# RobotCtrl_V2_Core-board.net
KiCad netlist of a schematic drawn in Altium Designer
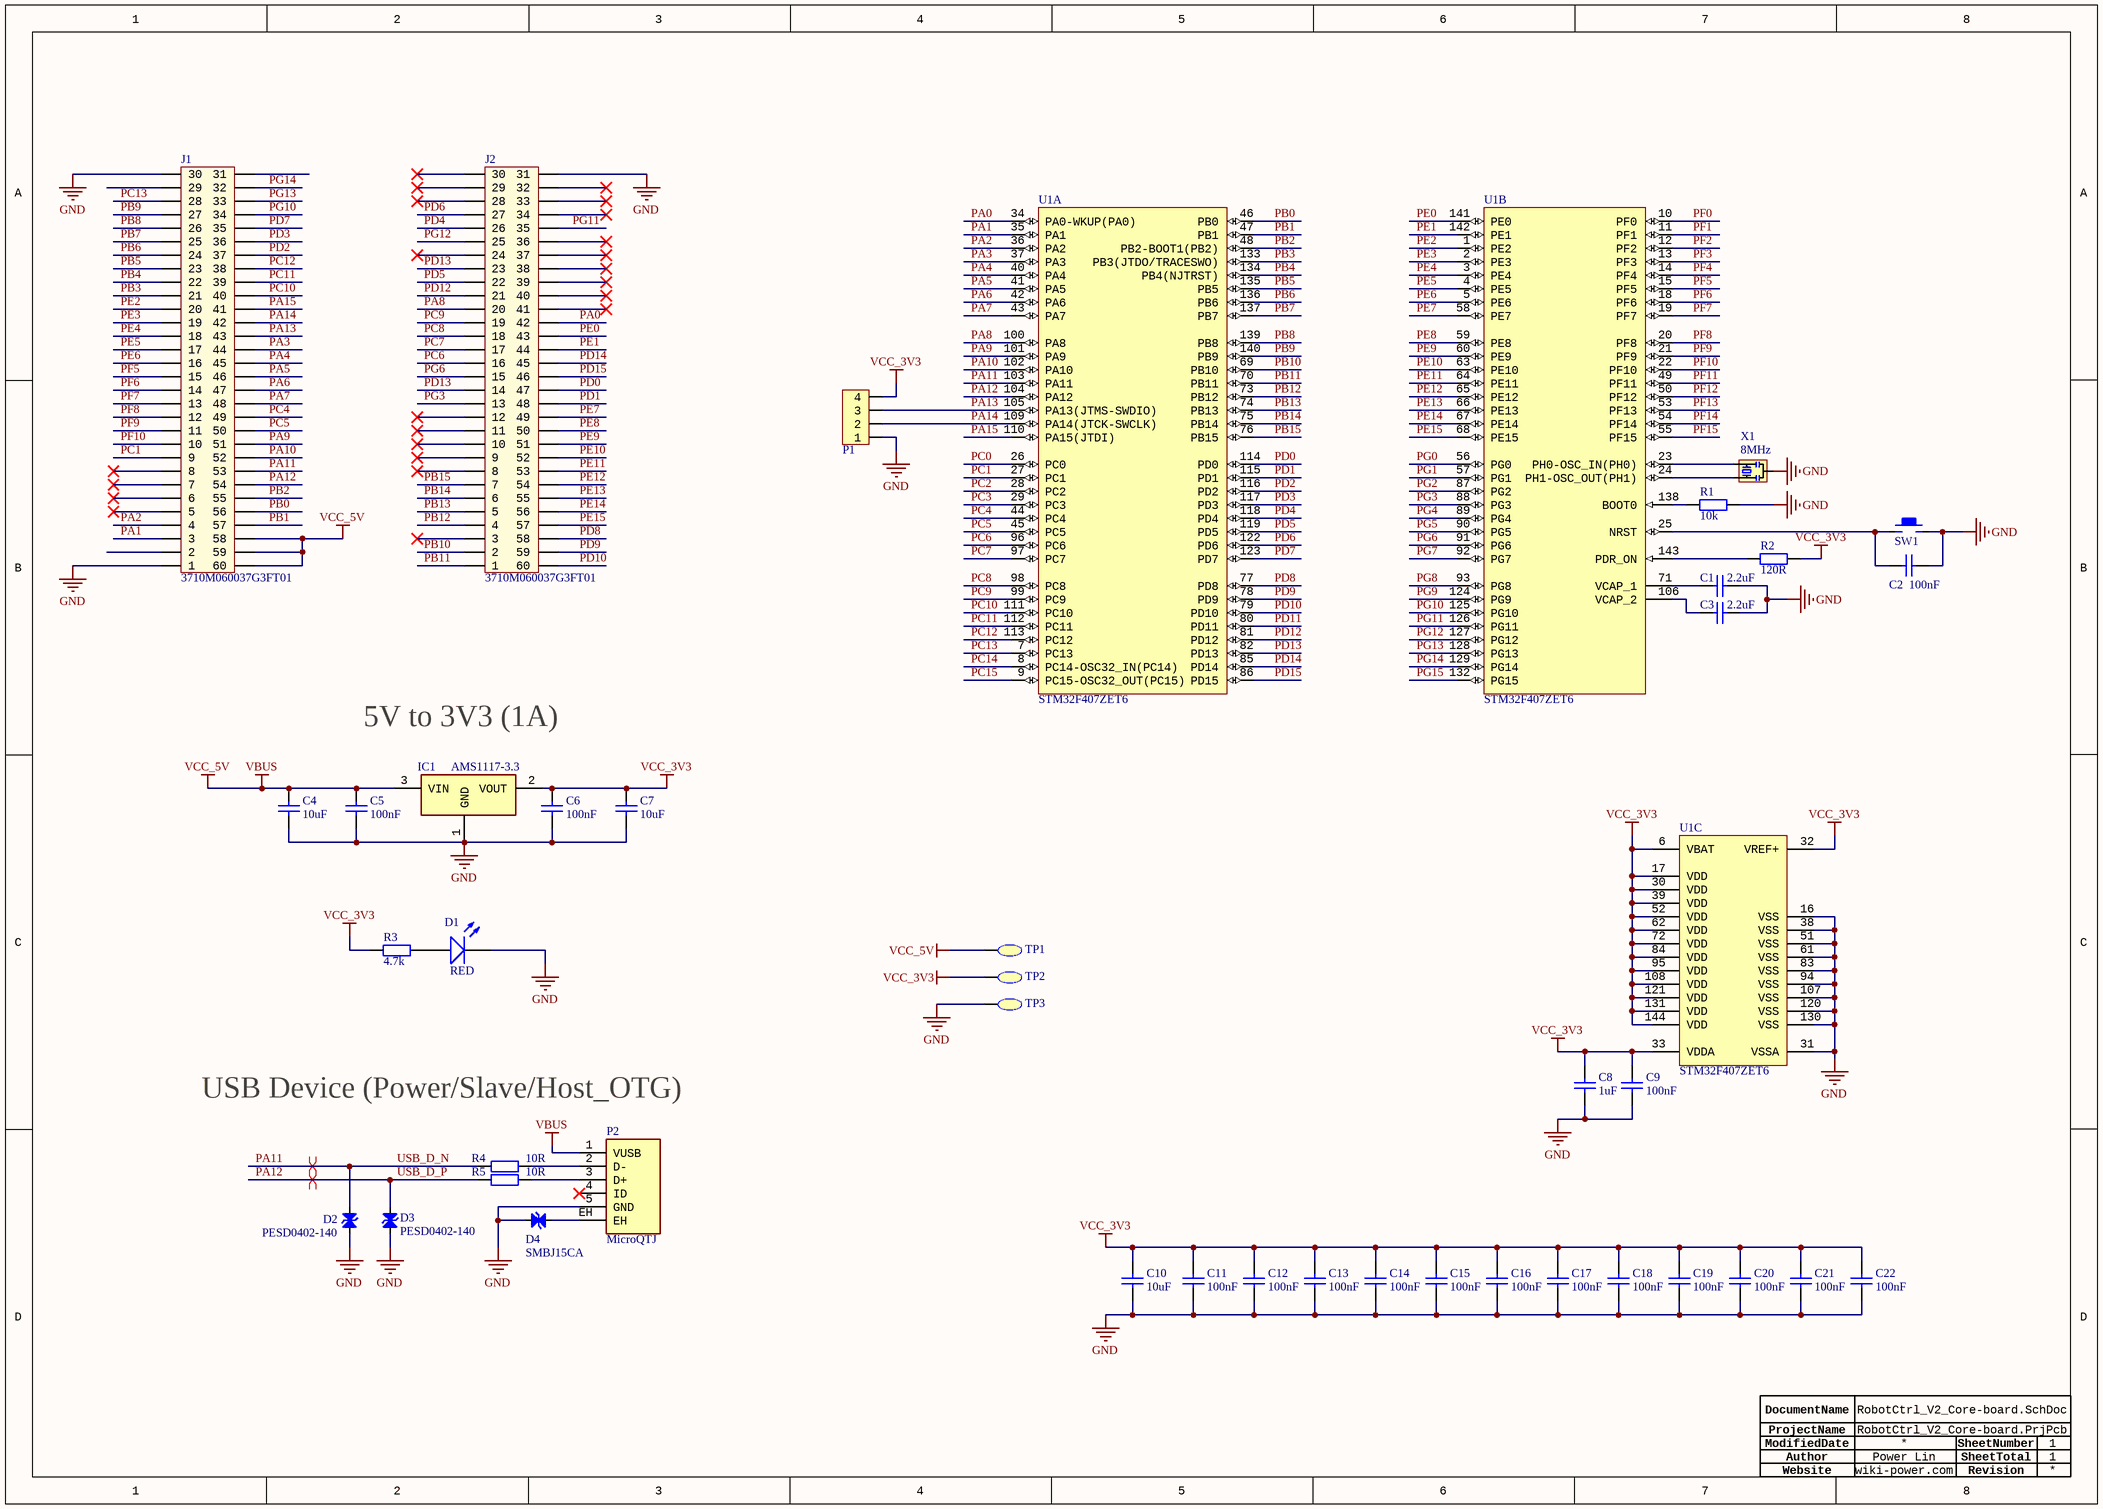
[diagram p0: RobotCtrl_V2_Core-board.SchDoc]

(export (version "E")
  (design (tool "Eeschema 10.0.6"))
  (components
    (comp (ref "C1")
      (value "2.2uF")
      (footprint "CAP-0603")
      (description "贴片电容")
      (libsource (lib "Power_Lib_Altium") (part "CAP"))
    )
    (comp (ref "C2")
      (value "100nF")
      (footprint "CAP-0603")
      (description "贴片电容")
      (libsource (lib "Power_Lib_Altium") (part "CAP"))
    )
    (comp (ref "C3")
      (value "2.2uF")
      (footprint "CAP-0603")
      (description "贴片电容")
      (libsource (lib "Power_Lib_Altium") (part "CAP"))
    )
    (comp (ref "C4")
      (value "10uF")
      (footprint "CAP-0603")
      (description "贴片电容")
      (libsource (lib "Power_Lib_Altium") (part "CAP"))
    )
    (comp (ref "C5")
      (value "100nF")
      (footprint "CAP-0603")
      (description "贴片电容")
      (libsource (lib "Power_Lib_Altium") (part "CAP"))
    )
    (comp (ref "C6")
      (value "100nF")
      (footprint "CAP-0603")
      (description "贴片电容")
      (libsource (lib "Power_Lib_Altium") (part "CAP"))
    )
    (comp (ref "C7")
      (value "10uF")
      (footprint "CAP-0603")
      (description "贴片电容")
      (libsource (lib "Power_Lib_Altium") (part "CAP"))
    )
    (comp (ref "C8")
      (value "1uF")
      (footprint "CAP-0603")
      (description "贴片电容")
      (libsource (lib "Power_Lib_Altium") (part "CAP"))
    )
    (comp (ref "C9")
      (value "100nF")
      (footprint "CAP-0603")
      (description "贴片电容")
      (libsource (lib "Power_Lib_Altium") (part "CAP"))
    )
    (comp (ref "C10")
      (value "10uF")
      (footprint "CAP-0603")
      (description "贴片电容")
      (libsource (lib "Power_Lib_Altium") (part "CAP"))
    )
    (comp (ref "C11")
      (value "100nF")
      (footprint "CAP-0603")
      (description "贴片电容")
      (libsource (lib "Power_Lib_Altium") (part "CAP"))
    )
    (comp (ref "C12")
      (value "100nF")
      (footprint "CAP-0603")
      (description "贴片电容")
      (libsource (lib "Power_Lib_Altium") (part "CAP"))
    )
    (comp (ref "C13")
      (value "100nF")
      (footprint "CAP-0603")
      (description "贴片电容")
      (libsource (lib "Power_Lib_Altium") (part "CAP"))
    )
    (comp (ref "C14")
      (value "100nF")
      (footprint "CAP-0603")
      (description "贴片电容")
      (libsource (lib "Power_Lib_Altium") (part "CAP"))
    )
    (comp (ref "C15")
      (value "100nF")
      (footprint "CAP-0603")
      (description "贴片电容")
      (libsource (lib "Power_Lib_Altium") (part "CAP"))
    )
    (comp (ref "C16")
      (value "100nF")
      (footprint "CAP-0603")
      (description "贴片电容")
      (libsource (lib "Power_Lib_Altium") (part "CAP"))
    )
    (comp (ref "C17")
      (value "100nF")
      (footprint "CAP-0603")
      (description "贴片电容")
      (libsource (lib "Power_Lib_Altium") (part "CAP"))
    )
    (comp (ref "C18")
      (value "100nF")
      (footprint "CAP-0603")
      (description "贴片电容")
      (libsource (lib "Power_Lib_Altium") (part "CAP"))
    )
    (comp (ref "C19")
      (value "100nF")
      (footprint "CAP-0603")
      (description "贴片电容")
      (libsource (lib "Power_Lib_Altium") (part "CAP"))
    )
    (comp (ref "C20")
      (value "100nF")
      (footprint "CAP-0603")
      (description "贴片电容")
      (libsource (lib "Power_Lib_Altium") (part "CAP"))
    )
    (comp (ref "C21")
      (value "100nF")
      (footprint "CAP-0603")
      (description "贴片电容")
      (libsource (lib "Power_Lib_Altium") (part "CAP"))
    )
    (comp (ref "C22")
      (value "100nF")
      (footprint "CAP-0603")
      (description "贴片电容")
      (libsource (lib "Power_Lib_Altium") (part "CAP"))
    )
    (comp (ref "D1")
      (value "RED")
      (footprint "LED-0603")
      (description "发光二极管")
      (libsource (lib "Power_Lib_Altium") (part "LED"))
    )
    (comp (ref "D2")
      (value "PESD0402-140")
      (footprint "D-0402")
      (libsource (lib "Power_Lib_Altium") (part "TVS_C"))
    )
    (comp (ref "D3")
      (value "PESD0402-140")
      (footprint "D-0402")
      (libsource (lib "Power_Lib_Altium") (part "TVS_C"))
    )
    (comp (ref "D4")
      (value "SMBJ15CA")
      (footprint "DO-214AA/SMB")
      (libsource (lib "Power_Lib_Altium") (part "TVS_C"))
    )
    (comp (ref "IC1")
      (value "AMS1117-3.3")
      (footprint "SOT-223")
      (description "AMS1117-3.3 1.0A")
      (fields (field (name "MANUFACTURER_PART_NUMBER") "SI2302DS") (field (name "RS PART NUMBER") "7983053P"))
      (libsource (lib "Power_Lib_Altium") (part "AMS1117"))
    )
    (comp (ref "J1")
      (value "3710M060037G3FT01")
      (footprint "3710M060037G3FT01")
      (description "B2B Connector")
      (libsource (lib "Power_Lib_Altium") (part "3710M/F"))
    )
    (comp (ref "J2")
      (value "3710M060037G3FT01")
      (footprint "3710M060037G3FT01")
      (description "B2B Connector")
      (libsource (lib "Power_Lib_Altium") (part "3710M/F"))
    )
    (comp (ref "P1")
      (value "HDR1x4_2.54")
      (footprint "HDR1x4_2.54_180")
      (description "Header")
      (libsource (lib "Power_Lib_Altium") (part "HDR1x4_2.54"))
    )
    (comp (ref "P2")
      (value "MicroQTJ")
      (footprint "USB-MICRO")
      (description "USB_MICRO")
      (libsource (lib "Power_Lib_Altium") (part "USB_MICRO"))
    )
    (comp (ref "R1")
      (value "10k")
      (footprint "R-0603")
      (description "贴片电阻")
      (libsource (lib "") (part "RES_1"))
    )
    (comp (ref "R2")
      (value "120R")
      (footprint "R-0603")
      (description "贴片电阻")
      (libsource (lib "") (part "RES_1"))
    )
    (comp (ref "R3")
      (value "4.7k")
      (footprint "R-0603")
      (description "贴片电阻")
      (libsource (lib "") (part "RES_1"))
    )
    (comp (ref "R4")
      (value "10R")
      (footprint "R-0603")
      (description "贴片电阻")
      (libsource (lib "Power_Lib_Altium") (part "RES"))
    )
    (comp (ref "R5")
      (value "10R")
      (footprint "R-0603")
      (description "贴片电阻")
      (libsource (lib "Power_Lib_Altium") (part "RES"))
    )
    (comp (ref "SW1")
      (value "KEY")
      (footprint "KEY-4P-4.2*3.4*2.5")
      (description "按键开关")
      (libsource (lib "Power_Lib_Altium") (part "KEY"))
    )
    (comp (ref "TP1")
      (value "TestPoint")
      (footprint "TestPoint")
      (description "测试点")
      (libsource (lib "Power_Lib_Altium") (part "TestPoint"))
    )
    (comp (ref "TP2")
      (value "TestPoint")
      (footprint "TestPoint")
      (description "测试点")
      (libsource (lib "Power_Lib_Altium") (part "TestPoint"))
    )
    (comp (ref "TP3")
      (value "TestPoint")
      (footprint "TestPoint")
      (description "测试点")
      (libsource (lib "Power_Lib_Altium") (part "TestPoint"))
    )
    (comp (ref "U1")
      (value "STM32F407ZET6")
      (footprint "STM-LQFP144_N")
      (fields (field (name "MANUFACTURER") "STMicroelectronics"))
      (libsource (lib "Power_Lib_Altium") (part "STM32F407ZET6"))
    )
    (comp (ref "X1")
      (value "8MHz")
      (footprint "SMD3213-3P")
      (description "CSTCE8M00G15C99-R0")
      (libsource (lib "Power_Lib_Altium") (part "XTAL"))
    )
  )
  (nets
    (net (code "1") (name "/PA0") (class "Default")
      (node (ref "J2") (pin "42") (pinfunction "42_42") (pintype "passive"))
      (node (ref "U1") (pin "34") (pinfunction "PA0-WKUP(PA0)_34") (pintype "bidirectional"))
    )
    (net (code "2") (name "/PA1") (class "Default")
      (node (ref "J1") (pin "3") (pinfunction "3_3") (pintype "passive"))
      (node (ref "U1") (pin "35") (pinfunction "PA1_35") (pintype "bidirectional"))
    )
    (net (code "3") (name "/PA2") (class "Default")
      (node (ref "J1") (pin "4") (pinfunction "4_4") (pintype "passive"))
      (node (ref "U1") (pin "36") (pinfunction "PA2_36") (pintype "bidirectional"))
    )
    (net (code "4") (name "/PA3") (class "Default")
      (node (ref "J1") (pin "44") (pinfunction "44_44") (pintype "passive"))
      (node (ref "U1") (pin "37") (pinfunction "PA3_37") (pintype "bidirectional"))
    )
    (net (code "5") (name "/PA4") (class "Default")
      (node (ref "J1") (pin "45") (pinfunction "45_45") (pintype "passive"))
      (node (ref "U1") (pin "40") (pinfunction "PA4_40") (pintype "bidirectional"))
    )
    (net (code "6") (name "/PA5") (class "Default")
      (node (ref "J1") (pin "46") (pinfunction "46_46") (pintype "passive"))
      (node (ref "U1") (pin "41") (pinfunction "PA5_41") (pintype "bidirectional"))
    )
    (net (code "7") (name "/PA6") (class "Default")
      (node (ref "J1") (pin "47") (pinfunction "47_47") (pintype "passive"))
      (node (ref "U1") (pin "42") (pinfunction "PA6_42") (pintype "bidirectional"))
    )
    (net (code "8") (name "/PA7") (class "Default")
      (node (ref "J1") (pin "48") (pinfunction "48_48") (pintype "passive"))
      (node (ref "U1") (pin "43") (pinfunction "PA7_43") (pintype "bidirectional"))
    )
    (net (code "9") (name "/PA8") (class "Default")
      (node (ref "J2") (pin "20") (pinfunction "20_20") (pintype "passive"))
      (node (ref "U1") (pin "100") (pinfunction "PA8_100") (pintype "bidirectional"))
    )
    (net (code "10") (name "/PA9") (class "Default")
      (node (ref "J1") (pin "51") (pinfunction "51_51") (pintype "passive"))
      (node (ref "U1") (pin "101") (pinfunction "PA9_101") (pintype "bidirectional"))
    )
    (net (code "11") (name "/PA10") (class "Default")
      (node (ref "J1") (pin "52") (pinfunction "52_52") (pintype "passive"))
      (node (ref "U1") (pin "102") (pinfunction "PA10_102") (pintype "bidirectional"))
    )
    (net (code "12") (name "/PA11") (class "Default")
      (node (ref "D2") (pin "2") (pinfunction "2_2") (pintype "passive"))
      (node (ref "J1") (pin "53") (pinfunction "53_53") (pintype "passive"))
      (node (ref "R4") (pin "1") (pinfunction "1_1") (pintype "passive"))
      (node (ref "U1") (pin "103") (pinfunction "PA11_103") (pintype "bidirectional"))
    )
    (net (code "13") (name "/PA12") (class "Default")
      (node (ref "D3") (pin "2") (pinfunction "2_2") (pintype "passive"))
      (node (ref "J1") (pin "54") (pinfunction "54_54") (pintype "passive"))
      (node (ref "R5") (pin "1") (pinfunction "1_1") (pintype "passive"))
      (node (ref "U1") (pin "104") (pinfunction "PA12_104") (pintype "bidirectional"))
    )
    (net (code "14") (name "/PA13") (class "Default")
      (node (ref "J1") (pin "43") (pinfunction "43_43") (pintype "passive"))
      (node (ref "P1") (pin "3") (pinfunction "3_3") (pintype "passive"))
      (node (ref "U1") (pin "105") (pinfunction "PA13(JTMS-SWDIO)_105") (pintype "bidirectional"))
    )
    (net (code "15") (name "/PA14") (class "Default")
      (node (ref "J1") (pin "42") (pinfunction "42_42") (pintype "passive"))
      (node (ref "P1") (pin "2") (pinfunction "2_2") (pintype "passive"))
      (node (ref "U1") (pin "109") (pinfunction "PA14(JTCK-SWCLK)_109") (pintype "bidirectional"))
    )
    (net (code "16") (name "/PA15") (class "Default")
      (node (ref "J1") (pin "41") (pinfunction "41_41") (pintype "passive"))
      (node (ref "U1") (pin "110") (pinfunction "PA15(JTDI)_110") (pintype "bidirectional"))
    )
    (net (code "17") (name "/PB0") (class "Default")
      (node (ref "J1") (pin "56") (pinfunction "56_56") (pintype "passive"))
      (node (ref "U1") (pin "46") (pinfunction "PB0_46") (pintype "bidirectional"))
    )
    (net (code "18") (name "/PB1") (class "Default")
      (node (ref "J1") (pin "57") (pinfunction "57_57") (pintype "passive"))
      (node (ref "U1") (pin "47") (pinfunction "PB1_47") (pintype "bidirectional"))
    )
    (net (code "19") (name "/PB2") (class "Default")
      (node (ref "J1") (pin "55") (pinfunction "55_55") (pintype "passive"))
      (node (ref "U1") (pin "48") (pinfunction "PB2-BOOT1(PB2)_48") (pintype "bidirectional"))
    )
    (net (code "20") (name "/PB3") (class "Default")
      (node (ref "J1") (pin "21") (pinfunction "21_21") (pintype "passive"))
      (node (ref "U1") (pin "133") (pinfunction "PB3(JTDO/TRACESWO)_133") (pintype "bidirectional"))
    )
    (net (code "21") (name "/PB4") (class "Default")
      (node (ref "J1") (pin "22") (pinfunction "22_22") (pintype "passive"))
      (node (ref "U1") (pin "134") (pinfunction "PB4(NJTRST)_134") (pintype "bidirectional"))
    )
    (net (code "22") (name "/PB5") (class "Default")
      (node (ref "J1") (pin "23") (pinfunction "23_23") (pintype "passive"))
      (node (ref "U1") (pin "135") (pinfunction "PB5_135") (pintype "bidirectional"))
    )
    (net (code "23") (name "/PB6") (class "Default")
      (node (ref "J1") (pin "24") (pinfunction "24_24") (pintype "passive"))
      (node (ref "U1") (pin "136") (pinfunction "PB6_136") (pintype "bidirectional"))
    )
    (net (code "24") (name "/PB7") (class "Default")
      (node (ref "J1") (pin "25") (pinfunction "25_25") (pintype "passive"))
      (node (ref "U1") (pin "137") (pinfunction "PB7_137") (pintype "bidirectional"))
    )
    (net (code "25") (name "/PB8") (class "Default")
      (node (ref "J1") (pin "26") (pinfunction "26_26") (pintype "passive"))
      (node (ref "U1") (pin "139") (pinfunction "PB8_139") (pintype "bidirectional"))
    )
    (net (code "26") (name "/PB9") (class "Default")
      (node (ref "J1") (pin "27") (pinfunction "27_27") (pintype "passive"))
      (node (ref "U1") (pin "140") (pinfunction "PB9_140") (pintype "bidirectional"))
    )
    (net (code "27") (name "/PB10") (class "Default")
      (node (ref "J2") (pin "2") (pinfunction "2_2") (pintype "passive"))
      (node (ref "U1") (pin "69") (pinfunction "PB10_69") (pintype "bidirectional"))
    )
    (net (code "28") (name "/PB11") (class "Default")
      (node (ref "J2") (pin "1") (pinfunction "1_1") (pintype "passive"))
      (node (ref "U1") (pin "70") (pinfunction "PB11_70") (pintype "bidirectional"))
    )
    (net (code "29") (name "/PB12") (class "Default")
      (node (ref "J2") (pin "4") (pinfunction "4_4") (pintype "passive"))
      (node (ref "U1") (pin "73") (pinfunction "PB12_73") (pintype "bidirectional"))
    )
    (net (code "30") (name "/PB13") (class "Default")
      (node (ref "J2") (pin "5") (pinfunction "5_5") (pintype "passive"))
      (node (ref "U1") (pin "74") (pinfunction "PB13_74") (pintype "bidirectional"))
    )
    (net (code "31") (name "/PB14") (class "Default")
      (node (ref "J2") (pin "6") (pinfunction "6_6") (pintype "passive"))
      (node (ref "U1") (pin "75") (pinfunction "PB14_75") (pintype "bidirectional"))
    )
    (net (code "32") (name "/PB15") (class "Default")
      (node (ref "J2") (pin "7") (pinfunction "7_7") (pintype "passive"))
      (node (ref "U1") (pin "76") (pinfunction "PB15_76") (pintype "bidirectional"))
    )
    (net (code "33") (name "/PC0") (class "Default")
      (node (ref "U1") (pin "26") (pinfunction "PC0_26") (pintype "bidirectional"))
    )
    (net (code "34") (name "/PC1") (class "Default")
      (node (ref "J1") (pin "9") (pinfunction "9_9") (pintype "passive"))
      (node (ref "U1") (pin "27") (pinfunction "PC1_27") (pintype "bidirectional"))
    )
    (net (code "35") (name "/PC2") (class "Default")
      (node (ref "U1") (pin "28") (pinfunction "PC2_28") (pintype "bidirectional"))
    )
    (net (code "36") (name "/PC3") (class "Default")
      (node (ref "U1") (pin "29") (pinfunction "PC3_29") (pintype "bidirectional"))
    )
    (net (code "37") (name "/PC4") (class "Default")
      (node (ref "J1") (pin "49") (pinfunction "49_49") (pintype "passive"))
      (node (ref "U1") (pin "44") (pinfunction "PC4_44") (pintype "bidirectional"))
    )
    (net (code "38") (name "/PC5") (class "Default")
      (node (ref "J1") (pin "50") (pinfunction "50_50") (pintype "passive"))
      (node (ref "U1") (pin "45") (pinfunction "PC5_45") (pintype "bidirectional"))
    )
    (net (code "39") (name "/PC6") (class "Default")
      (node (ref "J2") (pin "16") (pinfunction "16_16") (pintype "passive"))
      (node (ref "U1") (pin "96") (pinfunction "PC6_96") (pintype "bidirectional"))
    )
    (net (code "40") (name "/PC7") (class "Default")
      (node (ref "J2") (pin "17") (pinfunction "17_17") (pintype "passive"))
      (node (ref "U1") (pin "97") (pinfunction "PC7_97") (pintype "bidirectional"))
    )
    (net (code "41") (name "/PC8") (class "Default")
      (node (ref "J2") (pin "18") (pinfunction "18_18") (pintype "passive"))
      (node (ref "U1") (pin "98") (pinfunction "PC8_98") (pintype "bidirectional"))
    )
    (net (code "42") (name "/PC9") (class "Default")
      (node (ref "J2") (pin "19") (pinfunction "19_19") (pintype "passive"))
      (node (ref "U1") (pin "99") (pinfunction "PC9_99") (pintype "bidirectional"))
    )
    (net (code "43") (name "/PC10") (class "Default")
      (node (ref "J1") (pin "40") (pinfunction "40_40") (pintype "passive"))
      (node (ref "U1") (pin "111") (pinfunction "PC10_111") (pintype "bidirectional"))
    )
    (net (code "44") (name "/PC11") (class "Default")
      (node (ref "J1") (pin "39") (pinfunction "39_39") (pintype "passive"))
      (node (ref "U1") (pin "112") (pinfunction "PC11_112") (pintype "bidirectional"))
    )
    (net (code "45") (name "/PC12") (class "Default")
      (node (ref "J1") (pin "38") (pinfunction "38_38") (pintype "passive"))
      (node (ref "U1") (pin "113") (pinfunction "PC12_113") (pintype "bidirectional"))
    )
    (net (code "46") (name "/PC13") (class "Default")
      (node (ref "J1") (pin "28") (pinfunction "28_28") (pintype "passive"))
      (node (ref "U1") (pin "7") (pinfunction "PC13_7") (pintype "bidirectional"))
    )
    (net (code "47") (name "/PC14") (class "Default")
      (node (ref "U1") (pin "8") (pinfunction "PC14-OSC32_IN(PC14)_8") (pintype "bidirectional"))
    )
    (net (code "48") (name "/PC15") (class "Default")
      (node (ref "U1") (pin "9") (pinfunction "PC15-OSC32_OUT(PC15)_9") (pintype "bidirectional"))
    )
    (net (code "49") (name "/PD0") (class "Default")
      (node (ref "J2") (pin "47") (pinfunction "47_47") (pintype "passive"))
      (node (ref "U1") (pin "114") (pinfunction "PD0_114") (pintype "bidirectional"))
    )
    (net (code "50") (name "/PD1") (class "Default")
      (node (ref "J2") (pin "48") (pinfunction "48_48") (pintype "passive"))
      (node (ref "U1") (pin "115") (pinfunction "PD1_115") (pintype "bidirectional"))
    )
    (net (code "51") (name "/PD2") (class "Default")
      (node (ref "J1") (pin "37") (pinfunction "37_37") (pintype "passive"))
      (node (ref "U1") (pin "116") (pinfunction "PD2_116") (pintype "bidirectional"))
    )
    (net (code "52") (name "/PD3") (class "Default")
      (node (ref "J1") (pin "36") (pinfunction "36_36") (pintype "passive"))
      (node (ref "U1") (pin "117") (pinfunction "PD3_117") (pintype "bidirectional"))
    )
    (net (code "53") (name "/PD4") (class "Default")
      (node (ref "J2") (pin "26") (pinfunction "26_26") (pintype "passive"))
      (node (ref "U1") (pin "118") (pinfunction "PD4_118") (pintype "bidirectional"))
    )
    (net (code "54") (name "/PD5") (class "Default")
      (node (ref "J2") (pin "22") (pinfunction "22_22") (pintype "passive"))
      (node (ref "U1") (pin "119") (pinfunction "PD5_119") (pintype "bidirectional"))
    )
    (net (code "55") (name "/PD6") (class "Default")
      (node (ref "J2") (pin "27") (pinfunction "27_27") (pintype "passive"))
      (node (ref "U1") (pin "122") (pinfunction "PD6_122") (pintype "bidirectional"))
    )
    (net (code "56") (name "/PD7") (class "Default")
      (node (ref "J1") (pin "35") (pinfunction "35_35") (pintype "passive"))
      (node (ref "U1") (pin "123") (pinfunction "PD7_123") (pintype "bidirectional"))
    )
    (net (code "57") (name "/PD8") (class "Default")
      (node (ref "J2") (pin "58") (pinfunction "58_58") (pintype "passive"))
      (node (ref "U1") (pin "77") (pinfunction "PD8_77") (pintype "bidirectional"))
    )
    (net (code "58") (name "/PD9") (class "Default")
      (node (ref "J2") (pin "59") (pinfunction "59_59") (pintype "passive"))
      (node (ref "U1") (pin "78") (pinfunction "PD9_78") (pintype "bidirectional"))
    )
    (net (code "59") (name "/PD10") (class "Default")
      (node (ref "J2") (pin "60") (pinfunction "60_60") (pintype "passive"))
      (node (ref "U1") (pin "79") (pinfunction "PD10_79") (pintype "bidirectional"))
    )
    (net (code "60") (name "/PD11") (class "Default")
      (node (ref "U1") (pin "80") (pinfunction "PD11_80") (pintype "bidirectional"))
    )
    (net (code "61") (name "/PD12") (class "Default")
      (node (ref "J2") (pin "21") (pinfunction "21_21") (pintype "passive"))
      (node (ref "U1") (pin "81") (pinfunction "PD12_81") (pintype "bidirectional"))
    )
    (net (code "62") (name "/PD13") (class "Default")
      (node (ref "J2") (pin "14") (pinfunction "14_14") (pintype "passive"))
      (node (ref "J2") (pin "23") (pinfunction "23_23") (pintype "passive"))
      (node (ref "U1") (pin "82") (pinfunction "PD13_82") (pintype "bidirectional"))
    )
    (net (code "63") (name "/PD14") (class "Default")
      (node (ref "J2") (pin "45") (pinfunction "45_45") (pintype "passive"))
      (node (ref "U1") (pin "85") (pinfunction "PD14_85") (pintype "bidirectional"))
    )
    (net (code "64") (name "/PD15") (class "Default")
      (node (ref "J2") (pin "46") (pinfunction "46_46") (pintype "passive"))
      (node (ref "U1") (pin "86") (pinfunction "PD15_86") (pintype "bidirectional"))
    )
    (net (code "65") (name "/PE0") (class "Default")
      (node (ref "J2") (pin "43") (pinfunction "43_43") (pintype "passive"))
      (node (ref "U1") (pin "141") (pinfunction "PE0_141") (pintype "bidirectional"))
    )
    (net (code "66") (name "/PE1") (class "Default")
      (node (ref "J2") (pin "44") (pinfunction "44_44") (pintype "passive"))
      (node (ref "U1") (pin "142") (pinfunction "PE1_142") (pintype "bidirectional"))
    )
    (net (code "67") (name "/PE2") (class "Default")
      (node (ref "J1") (pin "20") (pinfunction "20_20") (pintype "passive"))
      (node (ref "U1") (pin "1") (pinfunction "PE2_1") (pintype "bidirectional"))
    )
    (net (code "68") (name "/PE3") (class "Default")
      (node (ref "J1") (pin "19") (pinfunction "19_19") (pintype "passive"))
      (node (ref "U1") (pin "2") (pinfunction "PE3_2") (pintype "bidirectional"))
    )
    (net (code "69") (name "/PE4") (class "Default")
      (node (ref "J1") (pin "18") (pinfunction "18_18") (pintype "passive"))
      (node (ref "U1") (pin "3") (pinfunction "PE4_3") (pintype "bidirectional"))
    )
    (net (code "70") (name "/PE5") (class "Default")
      (node (ref "J1") (pin "17") (pinfunction "17_17") (pintype "passive"))
      (node (ref "U1") (pin "4") (pinfunction "PE5_4") (pintype "bidirectional"))
    )
    (net (code "71") (name "/PE6") (class "Default")
      (node (ref "J1") (pin "16") (pinfunction "16_16") (pintype "passive"))
      (node (ref "U1") (pin "5") (pinfunction "PE6_5") (pintype "bidirectional"))
    )
    (net (code "72") (name "/PE7") (class "Default")
      (node (ref "J2") (pin "49") (pinfunction "49_49") (pintype "passive"))
      (node (ref "U1") (pin "58") (pinfunction "PE7_58") (pintype "bidirectional"))
    )
    (net (code "73") (name "/PE8") (class "Default")
      (node (ref "J2") (pin "50") (pinfunction "50_50") (pintype "passive"))
      (node (ref "U1") (pin "59") (pinfunction "PE8_59") (pintype "bidirectional"))
    )
    (net (code "74") (name "/PE9") (class "Default")
      (node (ref "J2") (pin "51") (pinfunction "51_51") (pintype "passive"))
      (node (ref "U1") (pin "60") (pinfunction "PE9_60") (pintype "bidirectional"))
    )
    (net (code "75") (name "/PE10") (class "Default")
      (node (ref "J2") (pin "52") (pinfunction "52_52") (pintype "passive"))
      (node (ref "U1") (pin "63") (pinfunction "PE10_63") (pintype "bidirectional"))
    )
    (net (code "76") (name "/PE11") (class "Default")
      (node (ref "J2") (pin "53") (pinfunction "53_53") (pintype "passive"))
      (node (ref "U1") (pin "64") (pinfunction "PE11_64") (pintype "bidirectional"))
    )
    (net (code "77") (name "/PE12") (class "Default")
      (node (ref "J2") (pin "54") (pinfunction "54_54") (pintype "passive"))
      (node (ref "U1") (pin "65") (pinfunction "PE12_65") (pintype "bidirectional"))
    )
    (net (code "78") (name "/PE13") (class "Default")
      (node (ref "J2") (pin "55") (pinfunction "55_55") (pintype "passive"))
      (node (ref "U1") (pin "66") (pinfunction "PE13_66") (pintype "bidirectional"))
    )
    (net (code "79") (name "/PE14") (class "Default")
      (node (ref "J2") (pin "56") (pinfunction "56_56") (pintype "passive"))
      (node (ref "U1") (pin "67") (pinfunction "PE14_67") (pintype "bidirectional"))
    )
    (net (code "80") (name "/PE15") (class "Default")
      (node (ref "J2") (pin "57") (pinfunction "57_57") (pintype "passive"))
      (node (ref "U1") (pin "68") (pinfunction "PE15_68") (pintype "bidirectional"))
    )
    (net (code "81") (name "/PF0") (class "Default")
      (node (ref "U1") (pin "10") (pinfunction "PF0_10") (pintype "bidirectional"))
    )
    (net (code "82") (name "/PF1") (class "Default")
      (node (ref "U1") (pin "11") (pinfunction "PF1_11") (pintype "bidirectional"))
    )
    (net (code "83") (name "/PF2") (class "Default")
      (node (ref "U1") (pin "12") (pinfunction "PF2_12") (pintype "bidirectional"))
    )
    (net (code "84") (name "/PF3") (class "Default")
      (node (ref "U1") (pin "13") (pinfunction "PF3_13") (pintype "bidirectional"))
    )
    (net (code "85") (name "/PF4") (class "Default")
      (node (ref "U1") (pin "14") (pinfunction "PF4_14") (pintype "bidirectional"))
    )
    (net (code "86") (name "/PF5") (class "Default")
      (node (ref "J1") (pin "15") (pinfunction "15_15") (pintype "passive"))
      (node (ref "U1") (pin "15") (pinfunction "PF5_15") (pintype "bidirectional"))
    )
    (net (code "87") (name "/PF6") (class "Default")
      (node (ref "J1") (pin "14") (pinfunction "14_14") (pintype "passive"))
      (node (ref "U1") (pin "18") (pinfunction "PF6_18") (pintype "bidirectional"))
    )
    (net (code "88") (name "/PF7") (class "Default")
      (node (ref "J1") (pin "13") (pinfunction "13_13") (pintype "passive"))
      (node (ref "U1") (pin "19") (pinfunction "PF7_19") (pintype "bidirectional"))
    )
    (net (code "89") (name "/PF8") (class "Default")
      (node (ref "J1") (pin "12") (pinfunction "12_12") (pintype "passive"))
      (node (ref "U1") (pin "20") (pinfunction "PF8_20") (pintype "bidirectional"))
    )
    (net (code "90") (name "/PF9") (class "Default")
      (node (ref "J1") (pin "11") (pinfunction "11_11") (pintype "passive"))
      (node (ref "U1") (pin "21") (pinfunction "PF9_21") (pintype "bidirectional"))
    )
    (net (code "91") (name "/PF10") (class "Default")
      (node (ref "J1") (pin "10") (pinfunction "10_10") (pintype "passive"))
      (node (ref "U1") (pin "22") (pinfunction "PF10_22") (pintype "bidirectional"))
    )
    (net (code "92") (name "/PF11") (class "Default")
      (node (ref "U1") (pin "49") (pinfunction "PF11_49") (pintype "bidirectional"))
    )
    (net (code "93") (name "/PF12") (class "Default")
      (node (ref "U1") (pin "50") (pinfunction "PF12_50") (pintype "bidirectional"))
    )
    (net (code "94") (name "/PF13") (class "Default")
      (node (ref "U1") (pin "53") (pinfunction "PF13_53") (pintype "bidirectional"))
    )
    (net (code "95") (name "/PF14") (class "Default")
      (node (ref "U1") (pin "54") (pinfunction "PF14_54") (pintype "bidirectional"))
    )
    (net (code "96") (name "/PF15") (class "Default")
      (node (ref "U1") (pin "55") (pinfunction "PF15_55") (pintype "bidirectional"))
    )
    (net (code "97") (name "/PG0") (class "Default")
      (node (ref "U1") (pin "56") (pinfunction "PG0_56") (pintype "bidirectional"))
    )
    (net (code "98") (name "/PG1") (class "Default")
      (node (ref "U1") (pin "57") (pinfunction "PG1_57") (pintype "bidirectional"))
    )
    (net (code "99") (name "/PG2") (class "Default")
      (node (ref "U1") (pin "87") (pinfunction "PG2_87") (pintype "bidirectional"))
    )
    (net (code "100") (name "/PG3") (class "Default")
      (node (ref "J2") (pin "13") (pinfunction "13_13") (pintype "passive"))
      (node (ref "U1") (pin "88") (pinfunction "PG3_88") (pintype "bidirectional"))
    )
    (net (code "101") (name "/PG4") (class "Default")
      (node (ref "U1") (pin "89") (pinfunction "PG4_89") (pintype "bidirectional"))
    )
    (net (code "102") (name "/PG5") (class "Default")
      (node (ref "U1") (pin "90") (pinfunction "PG5_90") (pintype "bidirectional"))
    )
    (net (code "103") (name "/PG6") (class "Default")
      (node (ref "J2") (pin "15") (pinfunction "15_15") (pintype "passive"))
      (node (ref "U1") (pin "91") (pinfunction "PG6_91") (pintype "bidirectional"))
    )
    (net (code "104") (name "/PG7") (class "Default")
      (node (ref "U1") (pin "92") (pinfunction "PG7_92") (pintype "bidirectional"))
    )
    (net (code "105") (name "/PG8") (class "Default")
      (node (ref "U1") (pin "93") (pinfunction "PG8_93") (pintype "bidirectional"))
    )
    (net (code "106") (name "/PG9") (class "Default")
      (node (ref "U1") (pin "124") (pinfunction "PG9_124") (pintype "bidirectional"))
    )
    (net (code "107") (name "/PG10") (class "Default")
      (node (ref "J1") (pin "34") (pinfunction "34_34") (pintype "passive"))
      (node (ref "U1") (pin "125") (pinfunction "PG10_125") (pintype "bidirectional"))
    )
    (net (code "108") (name "/PG11") (class "Default")
      (node (ref "J2") (pin "35") (pinfunction "35_35") (pintype "passive"))
      (node (ref "U1") (pin "126") (pinfunction "PG11_126") (pintype "bidirectional"))
    )
    (net (code "109") (name "/PG12") (class "Default")
      (node (ref "J2") (pin "25") (pinfunction "25_25") (pintype "passive"))
      (node (ref "U1") (pin "127") (pinfunction "PG12_127") (pintype "bidirectional"))
    )
    (net (code "110") (name "/PG13") (class "Default")
      (node (ref "J1") (pin "33") (pinfunction "33_33") (pintype "passive"))
      (node (ref "U1") (pin "128") (pinfunction "PG13_128") (pintype "bidirectional"))
    )
    (net (code "111") (name "/PG14") (class "Default")
      (node (ref "J1") (pin "32") (pinfunction "32_32") (pintype "passive"))
      (node (ref "U1") (pin "129") (pinfunction "PG14_129") (pintype "bidirectional"))
    )
    (net (code "112") (name "/PG15") (class "Default")
      (node (ref "U1") (pin "132") (pinfunction "PG15_132") (pintype "bidirectional"))
    )
    (net (code "113") (name "GND") (class "Default")
      (node (ref "C1") (pin "2") (pinfunction "2_2") (pintype "passive"))
      (node (ref "C10") (pin "1") (pinfunction "1_1") (pintype "passive"))
      (node (ref "C11") (pin "1") (pinfunction "1_1") (pintype "passive"))
      (node (ref "C12") (pin "1") (pinfunction "1_1") (pintype "passive"))
      (node (ref "C13") (pin "1") (pinfunction "1_1") (pintype "passive"))
      (node (ref "C14") (pin "1") (pinfunction "1_1") (pintype "passive"))
      (node (ref "C15") (pin "1") (pinfunction "1_1") (pintype "passive"))
      (node (ref "C16") (pin "1") (pinfunction "1_1") (pintype "passive"))
      (node (ref "C17") (pin "1") (pinfunction "1_1") (pintype "passive"))
      (node (ref "C18") (pin "1") (pinfunction "1_1") (pintype "passive"))
      (node (ref "C19") (pin "1") (pinfunction "1_1") (pintype "passive"))
      (node (ref "C2") (pin "1") (pinfunction "1_1") (pintype "passive"))
      (node (ref "C20") (pin "1") (pinfunction "1_1") (pintype "passive"))
      (node (ref "C21") (pin "1") (pinfunction "1_1") (pintype "passive"))
      (node (ref "C22") (pin "1") (pinfunction "1_1") (pintype "passive"))
      (node (ref "C3") (pin "2") (pinfunction "2_2") (pintype "passive"))
      (node (ref "C4") (pin "1") (pinfunction "1_1") (pintype "passive"))
      (node (ref "C5") (pin "1") (pinfunction "1_1") (pintype "passive"))
      (node (ref "C6") (pin "1") (pinfunction "1_1") (pintype "passive"))
      (node (ref "C7") (pin "1") (pinfunction "1_1") (pintype "passive"))
      (node (ref "C8") (pin "1") (pinfunction "1_1") (pintype "passive"))
      (node (ref "C9") (pin "1") (pinfunction "1_1") (pintype "passive"))
      (node (ref "D1") (pin "K") (pinfunction "K_K") (pintype "passive"))
      (node (ref "D2") (pin "1") (pinfunction "1_1") (pintype "passive"))
      (node (ref "D3") (pin "1") (pinfunction "1_1") (pintype "passive"))
      (node (ref "D4") (pin "2") (pinfunction "2_2") (pintype "passive"))
      (node (ref "IC1") (pin "1") (pinfunction "GND_1") (pintype "passive"))
      (node (ref "J1") (pin "1") (pinfunction "1_1") (pintype "passive"))
      (node (ref "J1") (pin "30") (pinfunction "30_30") (pintype "passive"))
      (node (ref "J2") (pin "31") (pinfunction "31_31") (pintype "passive"))
      (node (ref "P1") (pin "1") (pinfunction "1_1") (pintype "passive"))
      (node (ref "P2") (pin "5") (pinfunction "GND_5") (pintype "passive"))
      (node (ref "R1") (pin "1") (pinfunction "1_1") (pintype "passive"))
      (node (ref "SW1") (pin "2") (pinfunction "2_2") (pintype "passive"))
      (node (ref "TP3") (pin "1") (pinfunction "1_1") (pintype "passive"))
      (node (ref "U1") (pin "107") (pinfunction "VSS_107") (pintype "power_in"))
      (node (ref "U1") (pin "120") (pinfunction "VSS_120") (pintype "power_in"))
      (node (ref "U1") (pin "130") (pinfunction "VSS_130") (pintype "power_in"))
      (node (ref "U1") (pin "16") (pinfunction "VSS_16") (pintype "power_in"))
      (node (ref "U1") (pin "31") (pinfunction "VSSA_31") (pintype "power_in"))
      (node (ref "U1") (pin "38") (pinfunction "VSS_38") (pintype "power_in"))
      (node (ref "U1") (pin "51") (pinfunction "VSS_51") (pintype "power_in"))
      (node (ref "U1") (pin "61") (pinfunction "VSS_61") (pintype "power_in"))
      (node (ref "U1") (pin "83") (pinfunction "VSS_83") (pintype "power_in"))
      (node (ref "U1") (pin "94") (pinfunction "VSS_94") (pintype "power_in"))
      (node (ref "X1") (pin "2") (pinfunction "GND_2") (pintype "passive"))
    )
    (net (code "114") (name "Net-(D1-PadA)") (class "Default")
      (node (ref "D1") (pin "A") (pinfunction "A_A") (pintype "passive"))
      (node (ref "R3") (pin "1") (pinfunction "1_1") (pintype "passive"))
    )
    (net (code "115") (name "Net-(D4-Pad1)") (class "Default")
      (node (ref "D4") (pin "1") (pinfunction "1_1") (pintype "passive"))
      (node (ref "P2") (pin "EH") (pinfunction "EH_EH") (pintype "passive"))
    )
    (net (code "116") (name "Net-(P2-D+)") (class "Default")
      (node (ref "P2") (pin "3") (pinfunction "D+_3") (pintype "passive"))
      (node (ref "R5") (pin "2") (pinfunction "2_2") (pintype "passive"))
    )
    (net (code "117") (name "Net-(P2-D-)") (class "Default")
      (node (ref "P2") (pin "2") (pinfunction "D-_2") (pintype "passive"))
      (node (ref "R4") (pin "2") (pinfunction "2_2") (pintype "passive"))
    )
    (net (code "118") (name "Net-(U1B-BOOT0)") (class "Default")
      (node (ref "R1") (pin "2") (pinfunction "2_2") (pintype "passive"))
      (node (ref "U1") (pin "138") (pinfunction "BOOT0_138") (pintype "input"))
    )
    (net (code "119") (name "Net-(U1B-NRST)") (class "Default")
      (node (ref "C2") (pin "2") (pinfunction "2_2") (pintype "passive"))
      (node (ref "SW1") (pin "1") (pinfunction "1_1") (pintype "passive"))
      (node (ref "U1") (pin "25") (pinfunction "NRST_25") (pintype "bidirectional"))
    )
    (net (code "120") (name "Net-(U1B-PDR_ON)") (class "Default")
      (node (ref "R2") (pin "2") (pinfunction "2_2") (pintype "passive"))
      (node (ref "U1") (pin "143") (pinfunction "PDR_ON_143") (pintype "input"))
    )
    (net (code "121") (name "Net-(U1B-PH0-OSC_IN(PH0))") (class "Default")
      (node (ref "U1") (pin "23") (pinfunction "PH0-OSC_IN(PH0)_23") (pintype "bidirectional"))
      (node (ref "X1") (pin "3") (pinfunction "OSC2_3") (pintype "passive"))
    )
    (net (code "122") (name "Net-(U1B-PH1-OSC_OUT(PH1))") (class "Default")
      (node (ref "U1") (pin "24") (pinfunction "PH1-OSC_OUT(PH1)_24") (pintype "bidirectional"))
      (node (ref "X1") (pin "1") (pinfunction "OSC1_1") (pintype "passive"))
    )
    (net (code "123") (name "Net-(U1B-VCAP_1)") (class "Default")
      (node (ref "C1") (pin "1") (pinfunction "1_1") (pintype "passive"))
      (node (ref "U1") (pin "71") (pinfunction "VCAP_1_71") (pintype "power_in"))
    )
    (net (code "124") (name "Net-(U1B-VCAP_2)") (class "Default")
      (node (ref "C3") (pin "1") (pinfunction "1_1") (pintype "passive"))
      (node (ref "U1") (pin "106") (pinfunction "VCAP_2_106") (pintype "power_in"))
    )
    (net (code "125") (name "VBUS") (class "Default")
      (node (ref "C4") (pin "2") (pinfunction "2_2") (pintype "passive"))
      (node (ref "C5") (pin "2") (pinfunction "2_2") (pintype "passive"))
      (node (ref "IC1") (pin "3") (pinfunction "VIN_3") (pintype "passive"))
      (node (ref "J1") (pin "58") (pinfunction "58_58") (pintype "passive"))
      (node (ref "J1") (pin "59") (pinfunction "59_59") (pintype "passive"))
      (node (ref "J1") (pin "60") (pinfunction "60_60") (pintype "passive"))
      (node (ref "P2") (pin "1") (pinfunction "VUSB_1") (pintype "passive"))
      (node (ref "TP1") (pin "1") (pinfunction "1_1") (pintype "passive"))
    )
    (net (code "126") (name "VCC_3V3") (class "Default")
      (node (ref "C10") (pin "2") (pinfunction "2_2") (pintype "passive"))
      (node (ref "C11") (pin "2") (pinfunction "2_2") (pintype "passive"))
      (node (ref "C12") (pin "2") (pinfunction "2_2") (pintype "passive"))
      (node (ref "C13") (pin "2") (pinfunction "2_2") (pintype "passive"))
      (node (ref "C14") (pin "2") (pinfunction "2_2") (pintype "passive"))
      (node (ref "C15") (pin "2") (pinfunction "2_2") (pintype "passive"))
      (node (ref "C16") (pin "2") (pinfunction "2_2") (pintype "passive"))
      (node (ref "C17") (pin "2") (pinfunction "2_2") (pintype "passive"))
      (node (ref "C18") (pin "2") (pinfunction "2_2") (pintype "passive"))
      (node (ref "C19") (pin "2") (pinfunction "2_2") (pintype "passive"))
      (node (ref "C20") (pin "2") (pinfunction "2_2") (pintype "passive"))
      (node (ref "C21") (pin "2") (pinfunction "2_2") (pintype "passive"))
      (node (ref "C22") (pin "2") (pinfunction "2_2") (pintype "passive"))
      (node (ref "C6") (pin "2") (pinfunction "2_2") (pintype "passive"))
      (node (ref "C7") (pin "2") (pinfunction "2_2") (pintype "passive"))
      (node (ref "C8") (pin "2") (pinfunction "2_2") (pintype "passive"))
      (node (ref "C9") (pin "2") (pinfunction "2_2") (pintype "passive"))
      (node (ref "IC1") (pin "2") (pinfunction "VOUT_2") (pintype "passive"))
      (node (ref "P1") (pin "4") (pinfunction "4_4") (pintype "passive"))
      (node (ref "R2") (pin "1") (pinfunction "1_1") (pintype "passive"))
      (node (ref "R3") (pin "2") (pinfunction "2_2") (pintype "passive"))
      (node (ref "TP2") (pin "1") (pinfunction "1_1") (pintype "passive"))
      (node (ref "U1") (pin "108") (pinfunction "VDD_108") (pintype "power_in"))
      (node (ref "U1") (pin "121") (pinfunction "VDD_121") (pintype "power_in"))
      (node (ref "U1") (pin "131") (pinfunction "VDD_131") (pintype "power_in"))
      (node (ref "U1") (pin "144") (pinfunction "VDD_144") (pintype "power_in"))
      (node (ref "U1") (pin "17") (pinfunction "VDD_17") (pintype "power_in"))
      (node (ref "U1") (pin "30") (pinfunction "VDD_30") (pintype "power_in"))
      (node (ref "U1") (pin "32") (pinfunction "VREF+_32") (pintype "power_in"))
      (node (ref "U1") (pin "33") (pinfunction "VDDA_33") (pintype "power_in"))
      (node (ref "U1") (pin "39") (pinfunction "VDD_39") (pintype "power_in"))
      (node (ref "U1") (pin "52") (pinfunction "VDD_52") (pintype "power_in"))
      (node (ref "U1") (pin "6") (pinfunction "VBAT_6") (pintype "power_in"))
      (node (ref "U1") (pin "62") (pinfunction "VDD_62") (pintype "power_in"))
      (node (ref "U1") (pin "72") (pinfunction "VDD_72") (pintype "power_in"))
      (node (ref "U1") (pin "84") (pinfunction "VDD_84") (pintype "power_in"))
      (node (ref "U1") (pin "95") (pinfunction "VDD_95") (pintype "power_in"))
    )
    (net (code "127") (name "unconnected-(J1-Pad2)") (class "Default")
      (node (ref "J1") (pin "2") (pinfunction "2_2") (pintype "passive"))
    )
    (net (code "128") (name "unconnected-(J1-Pad5)") (class "Default")
      (node (ref "J1") (pin "5") (pinfunction "5_5") (pintype "passive+no_connect"))
    )
    (net (code "129") (name "unconnected-(J1-Pad6)") (class "Default")
      (node (ref "J1") (pin "6") (pinfunction "6_6") (pintype "passive+no_connect"))
    )
    (net (code "130") (name "unconnected-(J1-Pad7)") (class "Default")
      (node (ref "J1") (pin "7") (pinfunction "7_7") (pintype "passive+no_connect"))
    )
    (net (code "131") (name "unconnected-(J1-Pad8)") (class "Default")
      (node (ref "J1") (pin "8") (pinfunction "8_8") (pintype "passive+no_connect"))
    )
    (net (code "132") (name "unconnected-(J1-Pad29)") (class "Default")
      (node (ref "J1") (pin "29") (pinfunction "29_29") (pintype "passive"))
    )
    (net (code "133") (name "unconnected-(J1-Pad31)") (class "Default")
      (node (ref "J1") (pin "31") (pinfunction "31_31") (pintype "passive"))
    )
    (net (code "134") (name "unconnected-(J2-Pad3)") (class "Default")
      (node (ref "J2") (pin "3") (pinfunction "3_3") (pintype "passive+no_connect"))
    )
    (net (code "135") (name "unconnected-(J2-Pad8)") (class "Default")
      (node (ref "J2") (pin "8") (pinfunction "8_8") (pintype "passive+no_connect"))
    )
    (net (code "136") (name "unconnected-(J2-Pad9)") (class "Default")
      (node (ref "J2") (pin "9") (pinfunction "9_9") (pintype "passive+no_connect"))
    )
    (net (code "137") (name "unconnected-(J2-Pad10)") (class "Default")
      (node (ref "J2") (pin "10") (pinfunction "10_10") (pintype "passive+no_connect"))
    )
    (net (code "138") (name "unconnected-(J2-Pad11)") (class "Default")
      (node (ref "J2") (pin "11") (pinfunction "11_11") (pintype "passive+no_connect"))
    )
    (net (code "139") (name "unconnected-(J2-Pad12)") (class "Default")
      (node (ref "J2") (pin "12") (pinfunction "12_12") (pintype "passive+no_connect"))
    )
    (net (code "140") (name "unconnected-(J2-Pad24)") (class "Default")
      (node (ref "J2") (pin "24") (pinfunction "24_24") (pintype "passive+no_connect"))
    )
    (net (code "141") (name "unconnected-(J2-Pad28)") (class "Default")
      (node (ref "J2") (pin "28") (pinfunction "28_28") (pintype "passive+no_connect"))
    )
    (net (code "142") (name "unconnected-(J2-Pad29)") (class "Default")
      (node (ref "J2") (pin "29") (pinfunction "29_29") (pintype "passive+no_connect"))
    )
    (net (code "143") (name "unconnected-(J2-Pad30)") (class "Default")
      (node (ref "J2") (pin "30") (pinfunction "30_30") (pintype "passive+no_connect"))
    )
    (net (code "144") (name "unconnected-(J2-Pad32)") (class "Default")
      (node (ref "J2") (pin "32") (pinfunction "32_32") (pintype "passive+no_connect"))
    )
    (net (code "145") (name "unconnected-(J2-Pad33)") (class "Default")
      (node (ref "J2") (pin "33") (pinfunction "33_33") (pintype "passive+no_connect"))
    )
    (net (code "146") (name "unconnected-(J2-Pad34)") (class "Default")
      (node (ref "J2") (pin "34") (pinfunction "34_34") (pintype "passive+no_connect"))
    )
    (net (code "147") (name "unconnected-(J2-Pad36)") (class "Default")
      (node (ref "J2") (pin "36") (pinfunction "36_36") (pintype "passive+no_connect"))
    )
    (net (code "148") (name "unconnected-(J2-Pad37)") (class "Default")
      (node (ref "J2") (pin "37") (pinfunction "37_37") (pintype "passive+no_connect"))
    )
    (net (code "149") (name "unconnected-(J2-Pad38)") (class "Default")
      (node (ref "J2") (pin "38") (pinfunction "38_38") (pintype "passive+no_connect"))
    )
    (net (code "150") (name "unconnected-(J2-Pad39)") (class "Default")
      (node (ref "J2") (pin "39") (pinfunction "39_39") (pintype "passive+no_connect"))
    )
    (net (code "151") (name "unconnected-(J2-Pad40)") (class "Default")
      (node (ref "J2") (pin "40") (pinfunction "40_40") (pintype "passive+no_connect"))
    )
    (net (code "152") (name "unconnected-(J2-Pad41)") (class "Default")
      (node (ref "J2") (pin "41") (pinfunction "41_41") (pintype "passive+no_connect"))
    )
    (net (code "153") (name "unconnected-(P2-ID-Pad4)") (class "Default")
      (node (ref "P2") (pin "4") (pinfunction "ID_4") (pintype "passive+no_connect"))
    )
  )
)
